# CANbus.net
KiCad netlist of a schematic drawn in Altium Designer
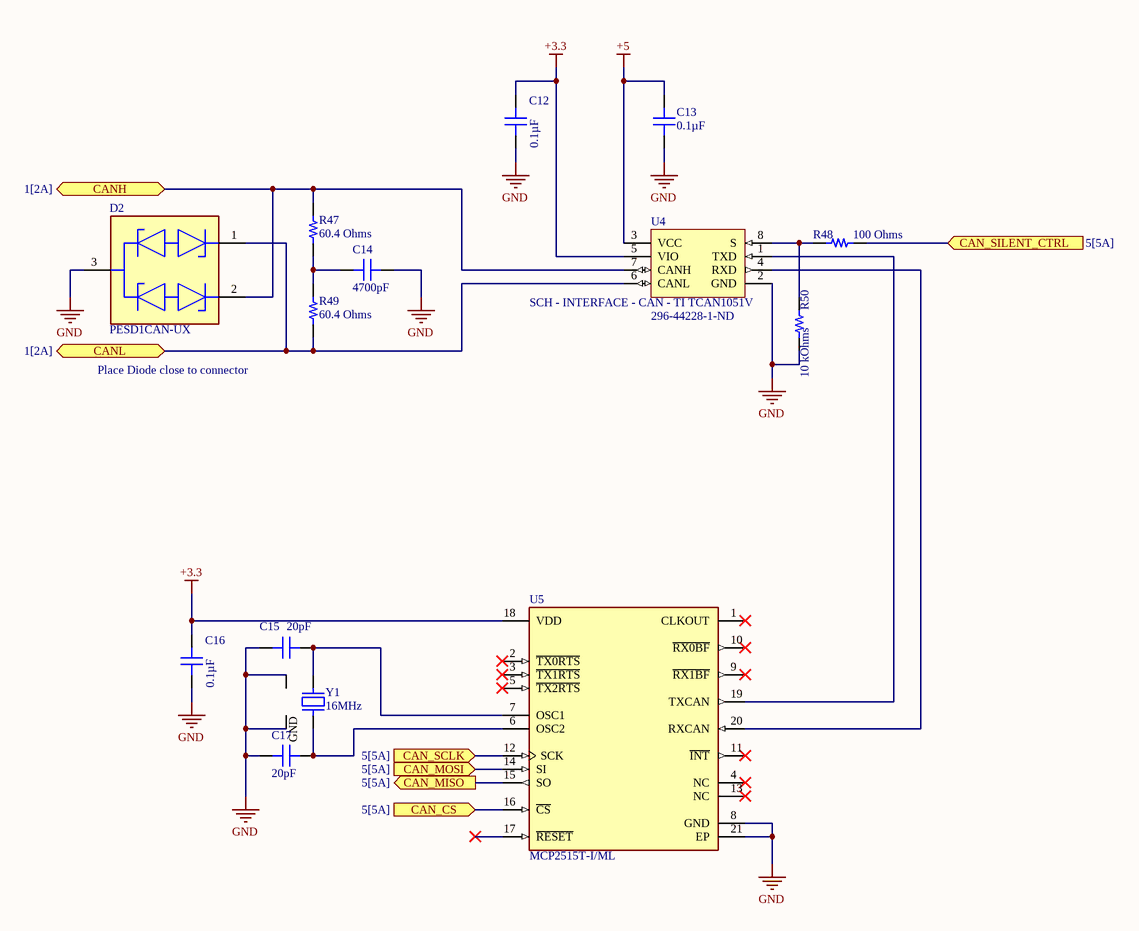
[diagram p0: CANbus.SchDoc]

(export (version "E")
  (design (tool "Eeschema 10.0.6"))
  (components
    (comp (ref "C12")
      (value "0.1µF")
      (footprint "CAP 0603_1608")
      (description "CAP CER 0.1UF 25V X7R 0603")
      (fields
        (field (name "PART NUMBER") "CL10B104KA8WPNC")
        (field (name "MANUFACTURER") "Samsung Electro-Mechanics")
      )
      (libsource (lib "Celestial Altium Library - altium_library") (part "Capacitor"))
    )
    (comp (ref "C13")
      (value "0.1µF")
      (footprint "CAP 0603_1608")
      (description "CAP CER 0.1UF 25V X7R 0603")
      (fields
        (field (name "PART NUMBER") "CL10B104KA8WPNC")
        (field (name "MANUFACTURER") "Samsung Electro-Mechanics")
      )
      (libsource (lib "Celestial Altium Library - altium_library") (part "Capacitor"))
    )
    (comp (ref "C14")
      (value "4700pF")
      (footprint "CAP 0603_1608")
      (description "CAP CER 4700PF 50V X7R 0603")
      (fields
        (field (name "PART NUMBER") "VJ0603Y472KXACW1BC")
        (field (name "MANUFACTURER") "Vishay Vitramon")
      )
      (libsource (lib "Celestial Altium Library - altium_library") (part "Capacitor"))
    )
    (comp (ref "C15")
      (value "20pF")
      (footprint "CAP 0603_1608")
      (description "CAP CER 20PF 50V C0G/NP0 0603")
      (fields
        (field (name "PART NUMBER") "CML0603C0G200JT50V")
        (field (name "MANUFACTURER") "Stackpole Electronics Inc")
      )
      (libsource (lib "Celestial Altium Library - altium_library") (part "Capacitor"))
    )
    (comp (ref "C16")
      (value "0.1µF")
      (footprint "CAP 0603_1608")
      (description "CAP CER 0.1UF 25V X7R 0603")
      (fields
        (field (name "PART NUMBER") "CL10B104KA8WPNC")
        (field (name "MANUFACTURER") "Samsung Electro-Mechanics")
      )
      (libsource (lib "Celestial Altium Library - altium_library") (part "Capacitor"))
    )
    (comp (ref "C17")
      (value "20pF")
      (footprint "CAP 0603_1608")
      (description "CAP CER 20PF 50V C0G/NP0 0603")
      (fields
        (field (name "PART NUMBER") "CML0603C0G200JT50V")
        (field (name "MANUFACTURER") "Stackpole Electronics Inc")
      )
      (libsource (lib "Celestial Altium Library - altium_library") (part "Capacitor"))
    )
    (comp (ref "D2")
      (value "PESD1CAN-UX")
      (footprint "FP-SOT323-MFG")
      (description "TVS DIODE 24V 50V SC70-3")
      (libsource (lib "Altium Content Vault") (part "04d57993b6b7b0f5b3c95ba4f97dea0"))
    )
    (comp (ref "R47")
      (value "60.4 Ohms")
      (footprint "RES 1206_3216")
      (description "RES SMD 60.4 OHM 1% 1/2W 1206")
      (fields (field (name "PART NUMBER") "ESR18EZPF60R4") (field (name "MANUFACTURER") "Rohm Semiconductor"))
      (libsource (lib "Celestial Altium Library - altium_library") (part "Resistor"))
    )
    (comp (ref "R48")
      (value "100 Ohms")
      (footprint "RES 0603_1608")
      (description "RES 100 OHM 1% 1/10W 0603")
      (fields
        (field (name "PART NUMBER") "RMCF0603FG100R")
        (field (name "MANUFACTURER") "Stackpole Electronics Inc")
      )
      (libsource (lib "Celestial Altium Library - altium_library") (part "Resistor"))
    )
    (comp (ref "R49")
      (value "60.4 Ohms")
      (footprint "RES 1206_3216")
      (description "RES SMD 60.4 OHM 1% 1/2W 1206")
      (fields (field (name "PART NUMBER") "ESR18EZPF60R4") (field (name "MANUFACTURER") "Rohm Semiconductor"))
      (libsource (lib "Celestial Altium Library - altium_library") (part "Resistor"))
    )
    (comp (ref "R50")
      (value "10 kOhms")
      (footprint "RES 0603_1608")
      (description "RES 10K OHM 5% 1/10W 0603")
      (fields
        (field (name "PART NUMBER") "RMCF0603JT10K0")
        (field (name "MANUFACTURER") "Stackpole Electronics Inc")
      )
      (libsource (lib "Celestial Altium Library - altium_library") (part "Resistor"))
    )
    (comp (ref "U4")
      (value "SCH - INTERFACE - CAN - TI TCAN1051V")
      (footprint "PCB - LEADS - SOIC - TI SOIC-8")
      (fields (field (name "SUPPLIER PART NUMBER 1") "296-44228-1-ND"))
      (libsource (lib "HAB_ICs") (part "SCH - INTERFACE - CAN - TI TCAN1051V"))
    )
    (comp (ref "U5")
      (value "MCP2515T-I/ML")
      (footprint "FP-C04-126-MFG")
      (description "IC CAN CTLR W/SPI 2.0B 20-QFN")
      (libsource (lib "Altium Content Vault") (part "593a678ea5bfa0b9d28ded8e5851c80"))
    )
    (comp (ref "Y1")
      (value "16MHz")
      (footprint "EPSON TSX-3225")
      (description "CRYSTAL 16.00 MHZ 16.0PF SMD")
      (fields (field (name "PART NUMBER") "TSX-3225 16.0000MF10U-B0") (field (name "MANUFACTURER") "EPSON"))
      (libsource (lib "Celestial Altium Library - altium_library") (part "Epson Crystal TSX-3225"))
    )
  )
  (nets
    (net (code "1") (name "+3.3") (class "Default")
      (node (ref "C12") (pin "2") (pinfunction "2_2") (pintype "passive"))
      (node (ref "C16") (pin "2") (pinfunction "2_2") (pintype "passive"))
      (node (ref "U4") (pin "5") (pinfunction "VIO_5") (pintype "power_in"))
      (node (ref "U5") (pin "18") (pinfunction "VDD_18") (pintype "power_in"))
    )
    (net (code "2") (name "+5") (class "Default")
      (node (ref "C13") (pin "2") (pinfunction "2_2") (pintype "passive"))
      (node (ref "U4") (pin "3") (pinfunction "VCC_3") (pintype "power_in"))
    )
    (net (code "3") (name "/CANH") (class "Default")
      (node (ref "D2") (pin "2") (pinfunction "cathode_2_2") (pintype "passive"))
      (node (ref "R47") (pin "2") (pinfunction "2_2") (pintype "passive"))
      (node (ref "U4") (pin "7") (pinfunction "CANH_7") (pintype "bidirectional"))
    )
    (net (code "4") (name "/CANL") (class "Default")
      (node (ref "D2") (pin "1") (pinfunction "cathode_1_1") (pintype "passive"))
      (node (ref "R49") (pin "1") (pinfunction "1_1") (pintype "passive"))
      (node (ref "U4") (pin "6") (pinfunction "CANL_6") (pintype "bidirectional"))
    )
    (net (code "5") (name "/CAN_CS") (class "Default")
      (node (ref "U5") (pin "16") (pinfunction "~{CS}_16") (pintype "input"))
    )
    (net (code "6") (name "/CAN_MISO") (class "Default")
      (node (ref "U5") (pin "15") (pinfunction "SO_15") (pintype "output"))
    )
    (net (code "7") (name "/CAN_MOSI") (class "Default")
      (node (ref "U5") (pin "14") (pinfunction "SI_14") (pintype "input"))
    )
    (net (code "8") (name "/CAN_SCLK") (class "Default")
      (node (ref "U5") (pin "12") (pinfunction "SCK_12") (pintype "input"))
    )
    (net (code "9") (name "/CAN_SILENT_CTRL") (class "Default")
      (node (ref "R48") (pin "2") (pinfunction "2_2") (pintype "passive"))
    )
    (net (code "10") (name "GND") (class "Default")
      (node (ref "C12") (pin "1") (pinfunction "1_1") (pintype "passive"))
      (node (ref "C13") (pin "1") (pinfunction "1_1") (pintype "passive"))
      (node (ref "C14") (pin "2") (pinfunction "2_2") (pintype "passive"))
      (node (ref "C15") (pin "1") (pinfunction "1_1") (pintype "passive"))
      (node (ref "C16") (pin "1") (pinfunction "1_1") (pintype "passive"))
      (node (ref "C17") (pin "1") (pinfunction "1_1") (pintype "passive"))
      (node (ref "D2") (pin "3") (pinfunction "common_cathode_3") (pintype "passive"))
      (node (ref "R50") (pin "1") (pinfunction "1_1") (pintype "passive"))
      (node (ref "U4") (pin "2") (pinfunction "GND_2") (pintype "power_in"))
      (node (ref "U5") (pin "21") (pinfunction "EP_21") (pintype "passive"))
      (node (ref "U5") (pin "8") (pinfunction "GND_8") (pintype "power_in"))
      (node (ref "Y1") (pin "2") (pinfunction "GND_2") (pintype "passive"))
      (node (ref "Y1") (pin "4") (pinfunction "GND_4") (pintype "passive"))
    )
    (net (code "11") (name "Net-(C14-Pad1)") (class "Default")
      (node (ref "C14") (pin "1") (pinfunction "1_1") (pintype "passive"))
      (node (ref "R47") (pin "1") (pinfunction "1_1") (pintype "passive"))
      (node (ref "R49") (pin "2") (pinfunction "2_2") (pintype "passive"))
    )
    (net (code "12") (name "Net-(U4-RXD)") (class "Default")
      (node (ref "U4") (pin "4") (pinfunction "RXD_4") (pintype "output"))
      (node (ref "U5") (pin "20") (pinfunction "RXCAN_20") (pintype "input"))
    )
    (net (code "13") (name "Net-(U4-S)") (class "Default")
      (node (ref "R48") (pin "1") (pinfunction "1_1") (pintype "passive"))
      (node (ref "R50") (pin "2") (pinfunction "2_2") (pintype "passive"))
      (node (ref "U4") (pin "8") (pinfunction "S_8") (pintype "input"))
    )
    (net (code "14") (name "Net-(U4-TXD)") (class "Default")
      (node (ref "U4") (pin "1") (pinfunction "TXD_1") (pintype "input"))
      (node (ref "U5") (pin "19") (pinfunction "TXCAN_19") (pintype "output"))
    )
    (net (code "15") (name "Net-(U5-OSC1)") (class "Default")
      (node (ref "C15") (pin "2") (pinfunction "2_2") (pintype "passive"))
      (node (ref "U5") (pin "7") (pinfunction "OSC1_7") (pintype "passive"))
      (node (ref "Y1") (pin "3") (pinfunction "3_3") (pintype "passive"))
    )
    (net (code "16") (name "Net-(U5-OSC2)") (class "Default")
      (node (ref "C17") (pin "2") (pinfunction "2_2") (pintype "passive"))
      (node (ref "U5") (pin "6") (pinfunction "OSC2_6") (pintype "passive"))
      (node (ref "Y1") (pin "1") (pinfunction "1_1") (pintype "passive"))
    )
    (net (code "17") (name "unconnected-(U5-CLKOUT-Pad1)") (class "Default")
      (node (ref "U5") (pin "1") (pinfunction "CLKOUT_1") (pintype "passive+no_connect"))
    )
    (net (code "18") (name "unconnected-(U5-NC-Pad4)") (class "Default")
      (node (ref "U5") (pin "4") (pinfunction "NC_4") (pintype "passive+no_connect"))
    )
    (net (code "19") (name "unconnected-(U5-NC-Pad13)") (class "Default")
      (node (ref "U5") (pin "13") (pinfunction "NC_13") (pintype "passive+no_connect"))
    )
    (net (code "20") (name "unconnected-(U5-~{INT}-Pad11)") (class "Default")
      (node (ref "U5") (pin "11") (pinfunction "~{INT}_11") (pintype "output+no_connect"))
    )
    (net (code "21") (name "unconnected-(U5-~{RESET}-Pad17)") (class "Default")
      (node (ref "U5") (pin "17") (pinfunction "~{RESET}_17") (pintype "input+no_connect"))
    )
    (net (code "22") (name "unconnected-(U5-~{RX0BF}-Pad10)") (class "Default")
      (node (ref "U5") (pin "10") (pinfunction "~{RX0BF}_10") (pintype "output+no_connect"))
    )
    (net (code "23") (name "unconnected-(U5-~{RX1BF}-Pad9)") (class "Default")
      (node (ref "U5") (pin "9") (pinfunction "~{RX1BF}_9") (pintype "output+no_connect"))
    )
    (net (code "24") (name "unconnected-(U5-~{TX0RTS}-Pad2)") (class "Default")
      (node (ref "U5") (pin "2") (pinfunction "~{TX0RTS}_2") (pintype "input+no_connect"))
    )
    (net (code "25") (name "unconnected-(U5-~{TX1RTS}-Pad3)") (class "Default")
      (node (ref "U5") (pin "3") (pinfunction "~{TX1RTS}_3") (pintype "input+no_connect"))
    )
    (net (code "26") (name "unconnected-(U5-~{TX2RTS}-Pad5)") (class "Default")
      (node (ref "U5") (pin "5") (pinfunction "~{TX2RTS}_5") (pintype "input+no_connect"))
    )
  )
)
